# M111B.net
KiCad netlist of a schematic drawn in EAGLE
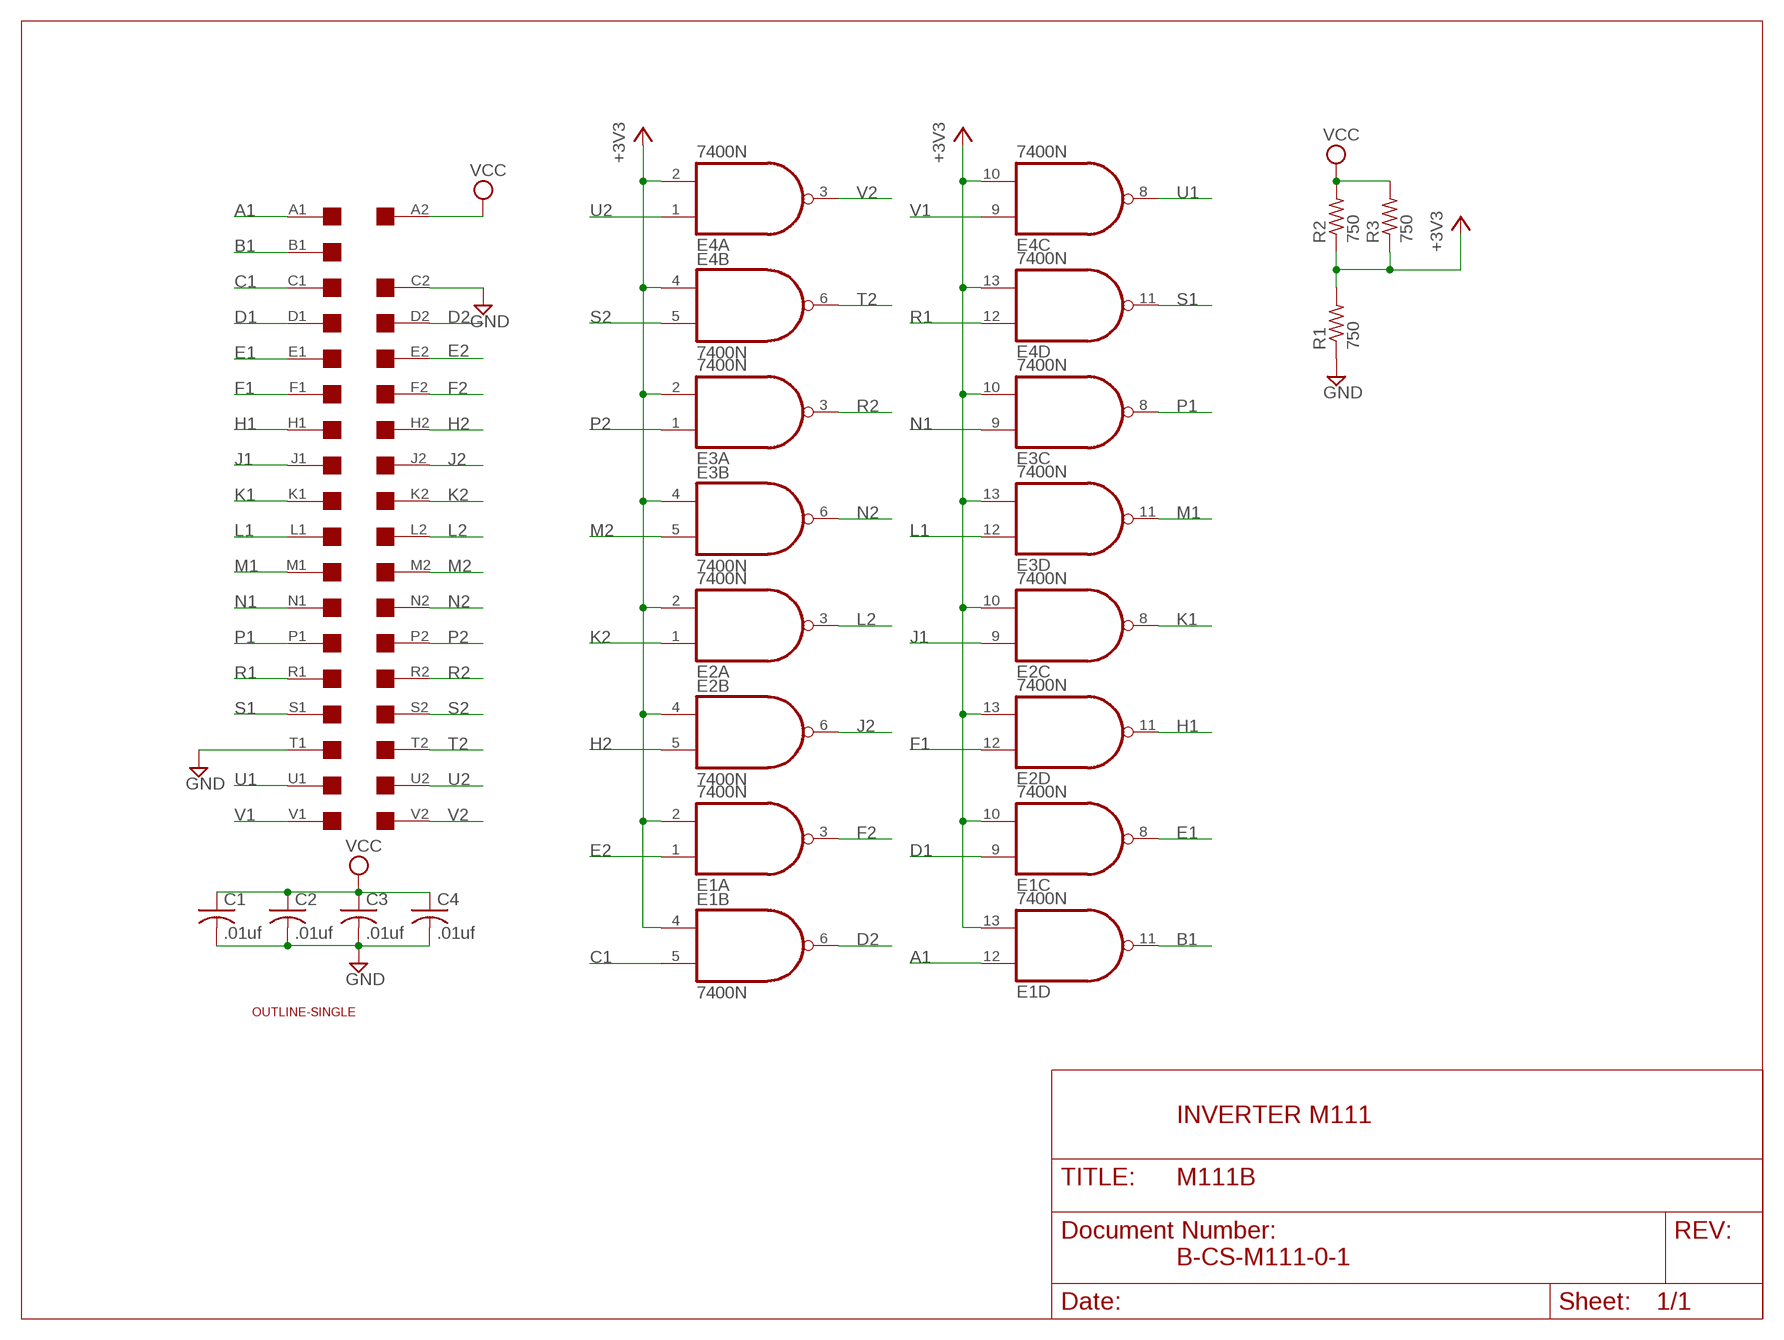
[diagram p0: schematic, sheet 1]

(export (version "E")
  (design (tool "Eeschema 10.0.6"))
  (components
    (comp (ref "A")
      (value "EDGE-2CONNECTOR")
      (footprint "eagle-import:EDGE-CON2")
      (libsource (lib "eagle-import") (part "EDGE-2CONNECTOR"))
    )
    (comp (ref "C1")
      (value ".01uf")
      (footprint "eagle-import:C050-025X075")
      (libsource (lib "eagle-import") (part "C-US050-025X075"))
    )
    (comp (ref "C2")
      (value ".01uf")
      (footprint "eagle-import:C050-025X075")
      (libsource (lib "eagle-import") (part "C-US050-025X075"))
    )
    (comp (ref "C3")
      (value ".01uf")
      (footprint "eagle-import:C050-025X075")
      (libsource (lib "eagle-import") (part "C-US050-025X075"))
    )
    (comp (ref "C4")
      (value ".01uf")
      (footprint "eagle-import:C050-025X075")
      (libsource (lib "eagle-import") (part "C-US050-025X075"))
    )
    (comp (ref "E1")
      (value "7400N")
      (footprint "eagle-import:DIL14")
      (libsource (lib "eagle-import") (part "7400N"))
    )
    (comp (ref "E2")
      (value "7400N")
      (footprint "eagle-import:DIL14")
      (libsource (lib "eagle-import") (part "7400N"))
    )
    (comp (ref "E3")
      (value "7400N")
      (footprint "eagle-import:DIL14")
      (libsource (lib "eagle-import") (part "7400N"))
    )
    (comp (ref "E4")
      (value "7400N")
      (footprint "eagle-import:DIL14")
      (libsource (lib "eagle-import") (part "7400N"))
    )
    (comp (ref "R1")
      (value "750")
      (footprint "eagle-import:0207_10")
      (libsource (lib "eagle-import") (part "R-US_0207/10"))
    )
    (comp (ref "R2")
      (value "750")
      (footprint "eagle-import:0207_10")
      (libsource (lib "eagle-import") (part "R-US_0207/10"))
    )
    (comp (ref "R3")
      (value "750")
      (footprint "eagle-import:0207_10")
      (libsource (lib "eagle-import") (part "R-US_0207/10"))
    )
    (comp (ref "U$1")
      (value "OUTLINE-SINGLE")
      (footprint "eagle-import:SINGLE")
      (libsource (lib "eagle-import") (part "OUTLINE-SINGLE"))
    )
  )
  (nets
    (net (code "1") (name "+3V3") (class "Default")
      (node (ref "E1") (pin "10") (pinfunction "I1_10") (pintype "input"))
      (node (ref "E1") (pin "13") (pinfunction "I1_13") (pintype "input"))
      (node (ref "E1") (pin "2") (pinfunction "I1_2") (pintype "input"))
      (node (ref "E1") (pin "4") (pinfunction "I0_4") (pintype "input"))
      (node (ref "E2") (pin "10") (pinfunction "I1_10") (pintype "input"))
      (node (ref "E2") (pin "13") (pinfunction "I1_13") (pintype "input"))
      (node (ref "E2") (pin "2") (pinfunction "I1_2") (pintype "input"))
      (node (ref "E2") (pin "4") (pinfunction "I0_4") (pintype "input"))
      (node (ref "E3") (pin "10") (pinfunction "I1_10") (pintype "input"))
      (node (ref "E3") (pin "13") (pinfunction "I1_13") (pintype "input"))
      (node (ref "E3") (pin "2") (pinfunction "I1_2") (pintype "input"))
      (node (ref "E3") (pin "4") (pinfunction "I0_4") (pintype "input"))
      (node (ref "E4") (pin "10") (pinfunction "I1_10") (pintype "input"))
      (node (ref "E4") (pin "13") (pinfunction "I1_13") (pintype "input"))
      (node (ref "E4") (pin "2") (pinfunction "I1_2") (pintype "input"))
      (node (ref "E4") (pin "4") (pinfunction "I0_4") (pintype "input"))
      (node (ref "R1") (pin "2") (pinfunction "2_2") (pintype "passive"))
      (node (ref "R2") (pin "1") (pinfunction "1_1") (pintype "passive"))
      (node (ref "R3") (pin "1") (pinfunction "1_1") (pintype "passive"))
    )
    (net (code "2") (name "/A1") (class "Default")
      (node (ref "A") (pin "A1") (pinfunction "1_A1") (pintype "bidirectional"))
      (node (ref "E1") (pin "12") (pinfunction "I0_12") (pintype "input"))
    )
    (net (code "3") (name "/B1") (class "Default")
      (node (ref "A") (pin "B1") (pinfunction "1_B1") (pintype "bidirectional"))
      (node (ref "E1") (pin "11") (pinfunction "O_11") (pintype "output"))
    )
    (net (code "4") (name "/C1") (class "Default")
      (node (ref "A") (pin "C1") (pinfunction "1_C1") (pintype "bidirectional"))
      (node (ref "E1") (pin "5") (pinfunction "I1_5") (pintype "input"))
    )
    (net (code "5") (name "/D1") (class "Default")
      (node (ref "A") (pin "D1") (pinfunction "1_D1") (pintype "bidirectional"))
      (node (ref "E1") (pin "9") (pinfunction "I0_9") (pintype "input"))
    )
    (net (code "6") (name "/D2") (class "Default")
      (node (ref "A") (pin "D2") (pinfunction "1_D2") (pintype "bidirectional"))
      (node (ref "E1") (pin "6") (pinfunction "O_6") (pintype "output"))
    )
    (net (code "7") (name "/E1") (class "Default")
      (node (ref "A") (pin "E1") (pinfunction "1_E1") (pintype "bidirectional"))
      (node (ref "E1") (pin "8") (pinfunction "O_8") (pintype "output"))
    )
    (net (code "8") (name "/E2") (class "Default")
      (node (ref "A") (pin "E2") (pinfunction "1_E2") (pintype "bidirectional"))
      (node (ref "E1") (pin "1") (pinfunction "I0_1") (pintype "input"))
    )
    (net (code "9") (name "/F1") (class "Default")
      (node (ref "A") (pin "F1") (pinfunction "1_F1") (pintype "bidirectional"))
      (node (ref "E2") (pin "12") (pinfunction "I0_12") (pintype "input"))
    )
    (net (code "10") (name "/F2") (class "Default")
      (node (ref "A") (pin "F2") (pinfunction "1_F2") (pintype "bidirectional"))
      (node (ref "E1") (pin "3") (pinfunction "O_3") (pintype "output"))
    )
    (net (code "11") (name "/H1") (class "Default")
      (node (ref "A") (pin "H1") (pinfunction "1_H1") (pintype "bidirectional"))
      (node (ref "E2") (pin "11") (pinfunction "O_11") (pintype "output"))
    )
    (net (code "12") (name "/H2") (class "Default")
      (node (ref "A") (pin "H2") (pinfunction "1_H2") (pintype "bidirectional"))
      (node (ref "E2") (pin "5") (pinfunction "I1_5") (pintype "input"))
    )
    (net (code "13") (name "/J1") (class "Default")
      (node (ref "A") (pin "J1") (pinfunction "1_J1") (pintype "bidirectional"))
      (node (ref "E2") (pin "9") (pinfunction "I0_9") (pintype "input"))
    )
    (net (code "14") (name "/J2") (class "Default")
      (node (ref "A") (pin "J2") (pinfunction "1_J2") (pintype "bidirectional"))
      (node (ref "E2") (pin "6") (pinfunction "O_6") (pintype "output"))
    )
    (net (code "15") (name "/K1") (class "Default")
      (node (ref "A") (pin "K1") (pinfunction "1_K1") (pintype "bidirectional"))
      (node (ref "E2") (pin "8") (pinfunction "O_8") (pintype "output"))
    )
    (net (code "16") (name "/K2") (class "Default")
      (node (ref "A") (pin "K2") (pinfunction "1_K2") (pintype "bidirectional"))
      (node (ref "E2") (pin "1") (pinfunction "I0_1") (pintype "input"))
    )
    (net (code "17") (name "/L1") (class "Default")
      (node (ref "A") (pin "L1") (pinfunction "1_L1") (pintype "bidirectional"))
      (node (ref "E3") (pin "12") (pinfunction "I0_12") (pintype "input"))
    )
    (net (code "18") (name "/L2") (class "Default")
      (node (ref "A") (pin "L2") (pinfunction "1_L2") (pintype "bidirectional"))
      (node (ref "E2") (pin "3") (pinfunction "O_3") (pintype "output"))
    )
    (net (code "19") (name "/M1") (class "Default")
      (node (ref "A") (pin "M1") (pinfunction "1_M1") (pintype "bidirectional"))
      (node (ref "E3") (pin "11") (pinfunction "O_11") (pintype "output"))
    )
    (net (code "20") (name "/M2") (class "Default")
      (node (ref "A") (pin "M2") (pinfunction "1_M2") (pintype "bidirectional"))
      (node (ref "E3") (pin "5") (pinfunction "I1_5") (pintype "input"))
    )
    (net (code "21") (name "/N1") (class "Default")
      (node (ref "A") (pin "N1") (pinfunction "1_N1") (pintype "bidirectional"))
      (node (ref "E3") (pin "9") (pinfunction "I0_9") (pintype "input"))
    )
    (net (code "22") (name "/N2") (class "Default")
      (node (ref "A") (pin "N2") (pinfunction "1_N2") (pintype "bidirectional"))
      (node (ref "E3") (pin "6") (pinfunction "O_6") (pintype "output"))
    )
    (net (code "23") (name "/P1") (class "Default")
      (node (ref "A") (pin "P1") (pinfunction "1_P1") (pintype "bidirectional"))
      (node (ref "E3") (pin "8") (pinfunction "O_8") (pintype "output"))
    )
    (net (code "24") (name "/P2") (class "Default")
      (node (ref "A") (pin "P2") (pinfunction "1_P2") (pintype "bidirectional"))
      (node (ref "E3") (pin "1") (pinfunction "I0_1") (pintype "input"))
    )
    (net (code "25") (name "/R1") (class "Default")
      (node (ref "A") (pin "R1") (pinfunction "1_R1") (pintype "bidirectional"))
      (node (ref "E4") (pin "12") (pinfunction "I0_12") (pintype "input"))
    )
    (net (code "26") (name "/R2") (class "Default")
      (node (ref "A") (pin "R2") (pinfunction "1_R2") (pintype "bidirectional"))
      (node (ref "E3") (pin "3") (pinfunction "O_3") (pintype "output"))
    )
    (net (code "27") (name "/S1") (class "Default")
      (node (ref "A") (pin "S1") (pinfunction "1_S1") (pintype "bidirectional"))
      (node (ref "E4") (pin "11") (pinfunction "O_11") (pintype "output"))
    )
    (net (code "28") (name "/S2") (class "Default")
      (node (ref "A") (pin "S2") (pinfunction "1_S2") (pintype "bidirectional"))
      (node (ref "E4") (pin "5") (pinfunction "I1_5") (pintype "input"))
    )
    (net (code "29") (name "/T2") (class "Default")
      (node (ref "A") (pin "T2") (pinfunction "1_T2") (pintype "bidirectional"))
      (node (ref "E4") (pin "6") (pinfunction "O_6") (pintype "output"))
    )
    (net (code "30") (name "/U1") (class "Default")
      (node (ref "A") (pin "U1") (pinfunction "1_U1") (pintype "bidirectional"))
      (node (ref "E4") (pin "8") (pinfunction "O_8") (pintype "output"))
    )
    (net (code "31") (name "/U2") (class "Default")
      (node (ref "A") (pin "U2") (pinfunction "1_U2") (pintype "bidirectional"))
      (node (ref "E4") (pin "1") (pinfunction "I0_1") (pintype "input"))
    )
    (net (code "32") (name "/V1") (class "Default")
      (node (ref "A") (pin "V1") (pinfunction "1_V1") (pintype "bidirectional"))
      (node (ref "E4") (pin "9") (pinfunction "I0_9") (pintype "input"))
    )
    (net (code "33") (name "/V2") (class "Default")
      (node (ref "A") (pin "V2") (pinfunction "1_V2") (pintype "bidirectional"))
      (node (ref "E4") (pin "3") (pinfunction "O_3") (pintype "output"))
    )
    (net (code "34") (name "GND") (class "Default")
      (node (ref "A") (pin "C2") (pinfunction "1_C2") (pintype "bidirectional"))
      (node (ref "A") (pin "T1") (pinfunction "1_T1") (pintype "bidirectional"))
      (node (ref "C1") (pin "2") (pinfunction "2_2") (pintype "passive"))
      (node (ref "C2") (pin "2") (pinfunction "2_2") (pintype "passive"))
      (node (ref "C3") (pin "2") (pinfunction "2_2") (pintype "passive"))
      (node (ref "C4") (pin "2") (pinfunction "2_2") (pintype "passive"))
      (node (ref "R1") (pin "1") (pinfunction "1_1") (pintype "passive"))
    )
    (net (code "35") (name "VCC") (class "Default")
      (node (ref "A") (pin "A2") (pinfunction "1_A2") (pintype "bidirectional"))
      (node (ref "C1") (pin "1") (pinfunction "1_1") (pintype "passive"))
      (node (ref "C2") (pin "1") (pinfunction "1_1") (pintype "passive"))
      (node (ref "C3") (pin "1") (pinfunction "1_1") (pintype "passive"))
      (node (ref "C4") (pin "1") (pinfunction "1_1") (pintype "passive"))
      (node (ref "R2") (pin "2") (pinfunction "2_2") (pintype "passive"))
      (node (ref "R3") (pin "2") (pinfunction "2_2") (pintype "passive"))
    )
  )
)
